# FPGA.net
KiCad netlist of a schematic drawn in Altium Designer
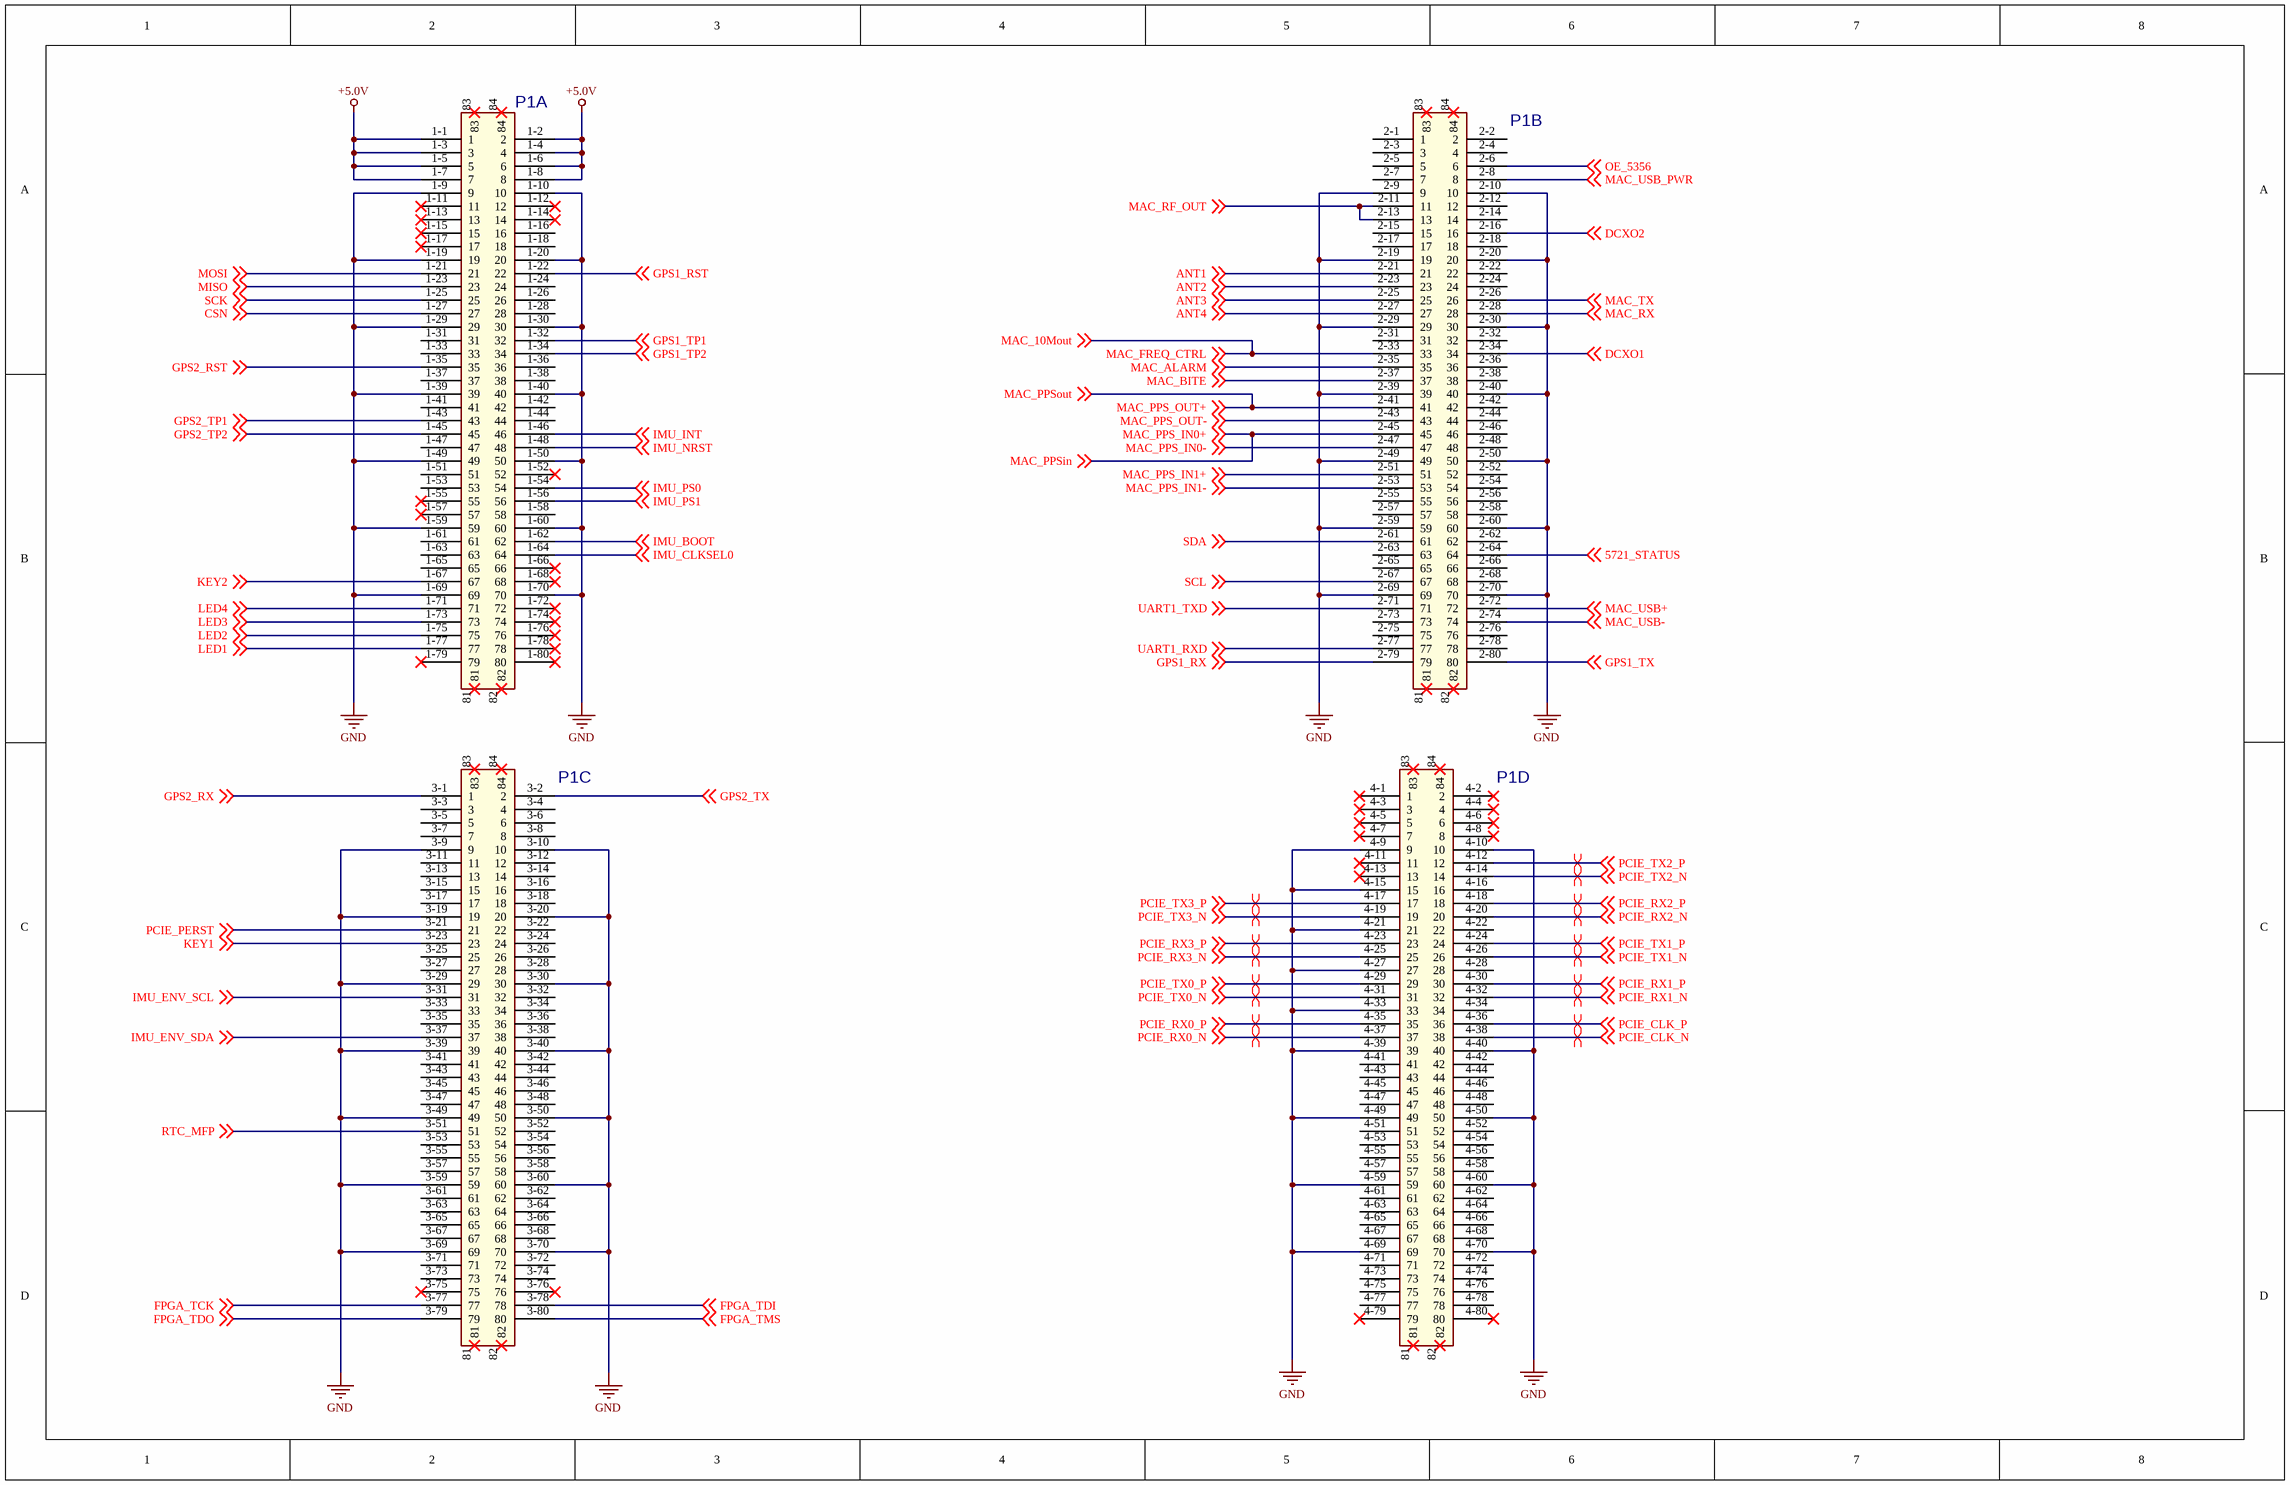
[diagram p0: FPGA.SchDoc]

(export (version "E")
  (design (tool "Eeschema 10.0.6"))
  (components
    (comp (ref "P1")
      (value "MOD, FPGA, AC7100")
      (footprint "ALINX_FPGA")
      (description "MOD, FPGA, AC7100")
      (fields (field (name "MFG PART NUM") "AXK680337YG") (field (name "VALENTIUM PART NUM") "<VALENTIUM>"))
      (libsource (lib "Modules") (part "ALINX_FPGA"))
    )
  )
  (nets
    (net (code "1") (name "+5.0V") (class "Default")
      (node (ref "P1") (pin "1-1") (pinfunction "1_1-1") (pintype "passive"))
      (node (ref "P1") (pin "1-2") (pinfunction "2_1-2") (pintype "passive"))
      (node (ref "P1") (pin "1-3") (pinfunction "3_1-3") (pintype "passive"))
      (node (ref "P1") (pin "1-4") (pinfunction "4_1-4") (pintype "passive"))
      (node (ref "P1") (pin "1-5") (pinfunction "5_1-5") (pintype "passive"))
      (node (ref "P1") (pin "1-6") (pinfunction "6_1-6") (pintype "passive"))
      (node (ref "P1") (pin "1-7") (pinfunction "7_1-7") (pintype "passive"))
      (node (ref "P1") (pin "1-8") (pinfunction "8_1-8") (pintype "passive"))
    )
    (net (code "2") (name "5721_STATUS") (class "Default")
      (node (ref "P1") (pin "2-64") (pinfunction "64_2-64") (pintype "passive"))
    )
    (net (code "3") (name "ANT1") (class "Default")
      (node (ref "P1") (pin "2-21") (pinfunction "21_2-21") (pintype "passive"))
    )
    (net (code "4") (name "ANT2") (class "Default")
      (node (ref "P1") (pin "2-23") (pinfunction "23_2-23") (pintype "passive"))
    )
    (net (code "5") (name "ANT3") (class "Default")
      (node (ref "P1") (pin "2-25") (pinfunction "25_2-25") (pintype "passive"))
    )
    (net (code "6") (name "ANT4") (class "Default")
      (node (ref "P1") (pin "2-27") (pinfunction "27_2-27") (pintype "passive"))
    )
    (net (code "7") (name "CSN") (class "Default")
      (node (ref "P1") (pin "1-27") (pinfunction "27_1-27") (pintype "passive"))
    )
    (net (code "8") (name "DCXO1") (class "Default")
      (node (ref "P1") (pin "2-34") (pinfunction "34_2-34") (pintype "passive"))
    )
    (net (code "9") (name "DCXO2") (class "Default")
      (node (ref "P1") (pin "2-16") (pinfunction "16_2-16") (pintype "passive"))
    )
    (net (code "10") (name "FPGA_TCK") (class "Default")
      (node (ref "P1") (pin "3-77") (pinfunction "77_3-77") (pintype "passive"))
    )
    (net (code "11") (name "FPGA_TDI") (class "Default")
      (node (ref "P1") (pin "3-78") (pinfunction "78_3-78") (pintype "passive"))
    )
    (net (code "12") (name "FPGA_TDO") (class "Default")
      (node (ref "P1") (pin "3-79") (pinfunction "79_3-79") (pintype "passive"))
    )
    (net (code "13") (name "FPGA_TMS") (class "Default")
      (node (ref "P1") (pin "3-80") (pinfunction "80_3-80") (pintype "passive"))
    )
    (net (code "14") (name "GND") (class "Default")
      (node (ref "P1") (pin "1-10") (pinfunction "10_1-10") (pintype "passive"))
      (node (ref "P1") (pin "1-19") (pinfunction "19_1-19") (pintype "passive"))
      (node (ref "P1") (pin "1-20") (pinfunction "20_1-20") (pintype "passive"))
      (node (ref "P1") (pin "1-29") (pinfunction "29_1-29") (pintype "passive"))
      (node (ref "P1") (pin "1-30") (pinfunction "30_1-30") (pintype "passive"))
      (node (ref "P1") (pin "1-39") (pinfunction "39_1-39") (pintype "passive"))
      (node (ref "P1") (pin "1-40") (pinfunction "40_1-40") (pintype "passive"))
      (node (ref "P1") (pin "1-49") (pinfunction "49_1-49") (pintype "passive"))
      (node (ref "P1") (pin "1-50") (pinfunction "50_1-50") (pintype "passive"))
      (node (ref "P1") (pin "1-59") (pinfunction "59_1-59") (pintype "passive"))
      (node (ref "P1") (pin "1-60") (pinfunction "60_1-60") (pintype "passive"))
      (node (ref "P1") (pin "1-69") (pinfunction "69_1-69") (pintype "passive"))
      (node (ref "P1") (pin "1-70") (pinfunction "70_1-70") (pintype "passive"))
      (node (ref "P1") (pin "1-9") (pinfunction "9_1-9") (pintype "passive"))
      (node (ref "P1") (pin "2-10") (pinfunction "10_2-10") (pintype "passive"))
      (node (ref "P1") (pin "2-19") (pinfunction "19_2-19") (pintype "passive"))
      (node (ref "P1") (pin "2-20") (pinfunction "20_2-20") (pintype "passive"))
      (node (ref "P1") (pin "2-29") (pinfunction "29_2-29") (pintype "passive"))
      (node (ref "P1") (pin "2-30") (pinfunction "30_2-30") (pintype "passive"))
      (node (ref "P1") (pin "2-39") (pinfunction "39_2-39") (pintype "passive"))
      (node (ref "P1") (pin "2-40") (pinfunction "40_2-40") (pintype "passive"))
      (node (ref "P1") (pin "2-49") (pinfunction "49_2-49") (pintype "passive"))
      (node (ref "P1") (pin "2-50") (pinfunction "50_2-50") (pintype "passive"))
      (node (ref "P1") (pin "2-59") (pinfunction "59_2-59") (pintype "passive"))
      (node (ref "P1") (pin "2-60") (pinfunction "60_2-60") (pintype "passive"))
      (node (ref "P1") (pin "2-69") (pinfunction "69_2-69") (pintype "passive"))
      (node (ref "P1") (pin "2-70") (pinfunction "70_2-70") (pintype "passive"))
      (node (ref "P1") (pin "2-9") (pinfunction "9_2-9") (pintype "passive"))
      (node (ref "P1") (pin "3-10") (pinfunction "10_3-10") (pintype "passive"))
      (node (ref "P1") (pin "3-19") (pinfunction "19_3-19") (pintype "passive"))
      (node (ref "P1") (pin "3-20") (pinfunction "20_3-20") (pintype "passive"))
      (node (ref "P1") (pin "3-29") (pinfunction "29_3-29") (pintype "passive"))
      (node (ref "P1") (pin "3-30") (pinfunction "30_3-30") (pintype "passive"))
      (node (ref "P1") (pin "3-39") (pinfunction "39_3-39") (pintype "passive"))
      (node (ref "P1") (pin "3-40") (pinfunction "40_3-40") (pintype "passive"))
      (node (ref "P1") (pin "3-49") (pinfunction "49_3-49") (pintype "passive"))
      (node (ref "P1") (pin "3-50") (pinfunction "50_3-50") (pintype "passive"))
      (node (ref "P1") (pin "3-59") (pinfunction "59_3-59") (pintype "passive"))
      (node (ref "P1") (pin "3-60") (pinfunction "60_3-60") (pintype "passive"))
      (node (ref "P1") (pin "3-69") (pinfunction "69_3-69") (pintype "passive"))
      (node (ref "P1") (pin "3-70") (pinfunction "70_3-70") (pintype "passive"))
      (node (ref "P1") (pin "3-9") (pinfunction "9_3-9") (pintype "passive"))
      (node (ref "P1") (pin "4-10") (pinfunction "10_4-10") (pintype "passive"))
      (node (ref "P1") (pin "4-15") (pinfunction "15_4-15") (pintype "passive"))
      (node (ref "P1") (pin "4-21") (pinfunction "21_4-21") (pintype "passive"))
      (node (ref "P1") (pin "4-27") (pinfunction "27_4-27") (pintype "passive"))
      (node (ref "P1") (pin "4-33") (pinfunction "33_4-33") (pintype "passive"))
      (node (ref "P1") (pin "4-39") (pinfunction "39_4-39") (pintype "passive"))
      (node (ref "P1") (pin "4-40") (pinfunction "40_4-40") (pintype "passive"))
      (node (ref "P1") (pin "4-49") (pinfunction "49_4-49") (pintype "passive"))
      (node (ref "P1") (pin "4-50") (pinfunction "50_4-50") (pintype "passive"))
      (node (ref "P1") (pin "4-59") (pinfunction "59_4-59") (pintype "passive"))
      (node (ref "P1") (pin "4-60") (pinfunction "60_4-60") (pintype "passive"))
      (node (ref "P1") (pin "4-69") (pinfunction "69_4-69") (pintype "passive"))
      (node (ref "P1") (pin "4-70") (pinfunction "70_4-70") (pintype "passive"))
      (node (ref "P1") (pin "4-9") (pinfunction "9_4-9") (pintype "passive"))
    )
    (net (code "15") (name "GPS1_RST") (class "Default")
      (node (ref "P1") (pin "1-22") (pinfunction "22_1-22") (pintype "passive"))
    )
    (net (code "16") (name "GPS1_RX") (class "Default")
      (node (ref "P1") (pin "2-79") (pinfunction "79_2-79") (pintype "passive"))
    )
    (net (code "17") (name "GPS1_TP1") (class "Default")
      (node (ref "P1") (pin "1-32") (pinfunction "32_1-32") (pintype "passive"))
    )
    (net (code "18") (name "GPS1_TP2") (class "Default")
      (node (ref "P1") (pin "1-34") (pinfunction "34_1-34") (pintype "passive"))
    )
    (net (code "19") (name "GPS1_TX") (class "Default")
      (node (ref "P1") (pin "2-80") (pinfunction "80_2-80") (pintype "passive"))
    )
    (net (code "20") (name "GPS2_RST") (class "Default")
      (node (ref "P1") (pin "1-35") (pinfunction "35_1-35") (pintype "passive"))
    )
    (net (code "21") (name "GPS2_RX") (class "Default")
      (node (ref "P1") (pin "3-1") (pinfunction "1_3-1") (pintype "passive"))
    )
    (net (code "22") (name "GPS2_TP1") (class "Default")
      (node (ref "P1") (pin "1-43") (pinfunction "43_1-43") (pintype "passive"))
    )
    (net (code "23") (name "GPS2_TP2") (class "Default")
      (node (ref "P1") (pin "1-45") (pinfunction "45_1-45") (pintype "passive"))
    )
    (net (code "24") (name "GPS2_TX") (class "Default")
      (node (ref "P1") (pin "3-2") (pinfunction "2_3-2") (pintype "passive"))
    )
    (net (code "25") (name "IMU_BOOT") (class "Default")
      (node (ref "P1") (pin "1-62") (pinfunction "62_1-62") (pintype "passive"))
    )
    (net (code "26") (name "IMU_CLKSEL0") (class "Default")
      (node (ref "P1") (pin "1-64") (pinfunction "64_1-64") (pintype "passive"))
    )
    (net (code "27") (name "IMU_ENV_SCL") (class "Default")
      (node (ref "P1") (pin "3-31") (pinfunction "31_3-31") (pintype "passive"))
    )
    (net (code "28") (name "IMU_ENV_SDA") (class "Default")
      (node (ref "P1") (pin "3-37") (pinfunction "37_3-37") (pintype "passive"))
    )
    (net (code "29") (name "IMU_INT") (class "Default")
      (node (ref "P1") (pin "1-46") (pinfunction "46_1-46") (pintype "passive"))
    )
    (net (code "30") (name "IMU_NRST") (class "Default")
      (node (ref "P1") (pin "1-48") (pinfunction "48_1-48") (pintype "passive"))
    )
    (net (code "31") (name "IMU_PS0") (class "Default")
      (node (ref "P1") (pin "1-54") (pinfunction "54_1-54") (pintype "passive"))
    )
    (net (code "32") (name "IMU_PS1") (class "Default")
      (node (ref "P1") (pin "1-56") (pinfunction "56_1-56") (pintype "passive"))
    )
    (net (code "33") (name "KEY1") (class "Default")
      (node (ref "P1") (pin "3-23") (pinfunction "23_3-23") (pintype "passive"))
    )
    (net (code "34") (name "KEY2") (class "Default")
      (node (ref "P1") (pin "1-67") (pinfunction "67_1-67") (pintype "passive"))
    )
    (net (code "35") (name "LED1") (class "Default")
      (node (ref "P1") (pin "1-77") (pinfunction "77_1-77") (pintype "passive"))
    )
    (net (code "36") (name "LED2") (class "Default")
      (node (ref "P1") (pin "1-75") (pinfunction "75_1-75") (pintype "passive"))
    )
    (net (code "37") (name "LED3") (class "Default")
      (node (ref "P1") (pin "1-73") (pinfunction "73_1-73") (pintype "passive"))
    )
    (net (code "38") (name "LED4") (class "Default")
      (node (ref "P1") (pin "1-71") (pinfunction "71_1-71") (pintype "passive"))
    )
    (net (code "39") (name "MAC_10Mout") (class "Default")
      (node (ref "P1") (pin "2-33") (pinfunction "33_2-33") (pintype "passive"))
    )
    (net (code "40") (name "MAC_ALARM") (class "Default")
      (node (ref "P1") (pin "2-35") (pinfunction "35_2-35") (pintype "passive"))
    )
    (net (code "41") (name "MAC_BITE") (class "Default")
      (node (ref "P1") (pin "2-37") (pinfunction "37_2-37") (pintype "passive"))
    )
    (net (code "42") (name "MAC_PPS_IN0+") (class "Default")
      (node (ref "P1") (pin "2-45") (pinfunction "45_2-45") (pintype "passive"))
    )
    (net (code "43") (name "MAC_PPS_IN0-") (class "Default")
      (node (ref "P1") (pin "2-47") (pinfunction "47_2-47") (pintype "passive"))
    )
    (net (code "44") (name "MAC_PPS_IN1+") (class "Default")
      (node (ref "P1") (pin "2-51") (pinfunction "51_2-51") (pintype "passive"))
    )
    (net (code "45") (name "MAC_PPS_IN1-") (class "Default")
      (node (ref "P1") (pin "2-53") (pinfunction "53_2-53") (pintype "passive"))
    )
    (net (code "46") (name "MAC_PPS_OUT+") (class "Default")
      (node (ref "P1") (pin "2-41") (pinfunction "41_2-41") (pintype "passive"))
    )
    (net (code "47") (name "MAC_PPS_OUT-") (class "Default")
      (node (ref "P1") (pin "2-43") (pinfunction "43_2-43") (pintype "passive"))
    )
    (net (code "48") (name "MAC_RF_OUT") (class "Default")
      (node (ref "P1") (pin "2-11") (pinfunction "11_2-11") (pintype "passive"))
      (node (ref "P1") (pin "2-13") (pinfunction "13_2-13") (pintype "passive"))
    )
    (net (code "49") (name "MAC_RX") (class "Default")
      (node (ref "P1") (pin "2-28") (pinfunction "28_2-28") (pintype "passive"))
    )
    (net (code "50") (name "MAC_TX") (class "Default")
      (node (ref "P1") (pin "2-26") (pinfunction "26_2-26") (pintype "passive"))
    )
    (net (code "51") (name "MAC_USB+") (class "Default")
      (node (ref "P1") (pin "2-72") (pinfunction "72_2-72") (pintype "passive"))
    )
    (net (code "52") (name "MAC_USB-") (class "Default")
      (node (ref "P1") (pin "2-74") (pinfunction "74_2-74") (pintype "passive"))
    )
    (net (code "53") (name "MAC_USB_PWR") (class "Default")
      (node (ref "P1") (pin "2-8") (pinfunction "8_2-8") (pintype "passive"))
    )
    (net (code "54") (name "MISO") (class "Default")
      (node (ref "P1") (pin "1-23") (pinfunction "23_1-23") (pintype "passive"))
    )
    (net (code "55") (name "MOSI") (class "Default")
      (node (ref "P1") (pin "1-21") (pinfunction "21_1-21") (pintype "passive"))
    )
    (net (code "56") (name "OE_5356") (class "Default")
      (node (ref "P1") (pin "2-6") (pinfunction "6_2-6") (pintype "passive"))
    )
    (net (code "57") (name "PCIE_CLK_N") (class "Default")
      (node (ref "P1") (pin "4-38") (pinfunction "38_4-38") (pintype "passive"))
    )
    (net (code "58") (name "PCIE_CLK_P") (class "Default")
      (node (ref "P1") (pin "4-36") (pinfunction "36_4-36") (pintype "passive"))
    )
    (net (code "59") (name "PCIE_PERST") (class "Default")
      (node (ref "P1") (pin "3-21") (pinfunction "21_3-21") (pintype "passive"))
    )
    (net (code "60") (name "PCIE_RX0_N") (class "Default")
      (node (ref "P1") (pin "4-37") (pinfunction "37_4-37") (pintype "passive"))
    )
    (net (code "61") (name "PCIE_RX0_P") (class "Default")
      (node (ref "P1") (pin "4-35") (pinfunction "35_4-35") (pintype "passive"))
    )
    (net (code "62") (name "PCIE_RX1_N") (class "Default")
      (node (ref "P1") (pin "4-32") (pinfunction "32_4-32") (pintype "passive"))
    )
    (net (code "63") (name "PCIE_RX1_P") (class "Default")
      (node (ref "P1") (pin "4-30") (pinfunction "30_4-30") (pintype "passive"))
    )
    (net (code "64") (name "PCIE_RX2_N") (class "Default")
      (node (ref "P1") (pin "4-20") (pinfunction "20_4-20") (pintype "passive"))
    )
    (net (code "65") (name "PCIE_RX2_P") (class "Default")
      (node (ref "P1") (pin "4-18") (pinfunction "18_4-18") (pintype "passive"))
    )
    (net (code "66") (name "PCIE_RX3_N") (class "Default")
      (node (ref "P1") (pin "4-25") (pinfunction "25_4-25") (pintype "passive"))
    )
    (net (code "67") (name "PCIE_RX3_P") (class "Default")
      (node (ref "P1") (pin "4-23") (pinfunction "23_4-23") (pintype "passive"))
    )
    (net (code "68") (name "PCIE_TX0_N") (class "Default")
      (node (ref "P1") (pin "4-31") (pinfunction "31_4-31") (pintype "passive"))
    )
    (net (code "69") (name "PCIE_TX0_P") (class "Default")
      (node (ref "P1") (pin "4-29") (pinfunction "29_4-29") (pintype "passive"))
    )
    (net (code "70") (name "PCIE_TX1_N") (class "Default")
      (node (ref "P1") (pin "4-26") (pinfunction "26_4-26") (pintype "passive"))
    )
    (net (code "71") (name "PCIE_TX1_P") (class "Default")
      (node (ref "P1") (pin "4-24") (pinfunction "24_4-24") (pintype "passive"))
    )
    (net (code "72") (name "PCIE_TX2_N") (class "Default")
      (node (ref "P1") (pin "4-14") (pinfunction "14_4-14") (pintype "passive"))
    )
    (net (code "73") (name "PCIE_TX2_P") (class "Default")
      (node (ref "P1") (pin "4-12") (pinfunction "12_4-12") (pintype "passive"))
    )
    (net (code "74") (name "PCIE_TX3_N") (class "Default")
      (node (ref "P1") (pin "4-19") (pinfunction "19_4-19") (pintype "passive"))
    )
    (net (code "75") (name "PCIE_TX3_P") (class "Default")
      (node (ref "P1") (pin "4-17") (pinfunction "17_4-17") (pintype "passive"))
    )
    (net (code "76") (name "RTC_MFP") (class "Default")
      (node (ref "P1") (pin "3-51") (pinfunction "51_3-51") (pintype "passive"))
    )
    (net (code "77") (name "SCK") (class "Default")
      (node (ref "P1") (pin "1-25") (pinfunction "25_1-25") (pintype "passive"))
    )
    (net (code "78") (name "SCL") (class "Default")
      (node (ref "P1") (pin "2-67") (pinfunction "67_2-67") (pintype "passive"))
    )
    (net (code "79") (name "SDA") (class "Default")
      (node (ref "P1") (pin "2-61") (pinfunction "61_2-61") (pintype "passive"))
    )
    (net (code "80") (name "UART1_RXD") (class "Default")
      (node (ref "P1") (pin "2-77") (pinfunction "77_2-77") (pintype "passive"))
    )
    (net (code "81") (name "UART1_TXD") (class "Default")
      (node (ref "P1") (pin "2-71") (pinfunction "71_2-71") (pintype "passive"))
    )
    (net (code "82") (name "unconnected-(P1-Pad81)") (class "Default")
      (node (ref "P1") (pin "81") (pinfunction "81_81") (pintype "passive+no_connect"))
    )
    (net (code "83") (name "unconnected-(P1-Pad81)_1") (class "Default")
      (node (ref "P1") (pin "81") (pinfunction "81_81") (pintype "passive+no_connect"))
    )
    (net (code "84") (name "unconnected-(P1-Pad81)_2") (class "Default")
      (node (ref "P1") (pin "81") (pinfunction "81_81") (pintype "passive+no_connect"))
    )
    (net (code "85") (name "unconnected-(P1-Pad81)_3") (class "Default")
      (node (ref "P1") (pin "81") (pinfunction "81_81") (pintype "passive+no_connect"))
    )
    (net (code "86") (name "unconnected-(P1-Pad82)") (class "Default")
      (node (ref "P1") (pin "82") (pinfunction "82_82") (pintype "passive+no_connect"))
    )
    (net (code "87") (name "unconnected-(P1-Pad82)_1") (class "Default")
      (node (ref "P1") (pin "82") (pinfunction "82_82") (pintype "passive+no_connect"))
    )
    (net (code "88") (name "unconnected-(P1-Pad82)_2") (class "Default")
      (node (ref "P1") (pin "82") (pinfunction "82_82") (pintype "passive+no_connect"))
    )
    (net (code "89") (name "unconnected-(P1-Pad82)_3") (class "Default")
      (node (ref "P1") (pin "82") (pinfunction "82_82") (pintype "passive+no_connect"))
    )
    (net (code "90") (name "unconnected-(P1-Pad83)") (class "Default")
      (node (ref "P1") (pin "83") (pinfunction "83_83") (pintype "passive+no_connect"))
    )
    (net (code "91") (name "unconnected-(P1-Pad83)_1") (class "Default")
      (node (ref "P1") (pin "83") (pinfunction "83_83") (pintype "passive+no_connect"))
    )
    (net (code "92") (name "unconnected-(P1-Pad83)_2") (class "Default")
      (node (ref "P1") (pin "83") (pinfunction "83_83") (pintype "passive+no_connect"))
    )
    (net (code "93") (name "unconnected-(P1-Pad83)_3") (class "Default")
      (node (ref "P1") (pin "83") (pinfunction "83_83") (pintype "passive+no_connect"))
    )
    (net (code "94") (name "unconnected-(P1-Pad84)") (class "Default")
      (node (ref "P1") (pin "84") (pinfunction "84_84") (pintype "passive+no_connect"))
    )
    (net (code "95") (name "unconnected-(P1-Pad84)_1") (class "Default")
      (node (ref "P1") (pin "84") (pinfunction "84_84") (pintype "passive+no_connect"))
    )
    (net (code "96") (name "unconnected-(P1-Pad84)_2") (class "Default")
      (node (ref "P1") (pin "84") (pinfunction "84_84") (pintype "passive+no_connect"))
    )
    (net (code "97") (name "unconnected-(P1-Pad84)_3") (class "Default")
      (node (ref "P1") (pin "84") (pinfunction "84_84") (pintype "passive+no_connect"))
    )
    (net (code "98") (name "unconnected-(P1A-11-Pad1-11)") (class "Default")
      (node (ref "P1") (pin "1-11") (pinfunction "11_1-11") (pintype "passive+no_connect"))
    )
    (net (code "99") (name "unconnected-(P1A-12-Pad1-12)") (class "Default")
      (node (ref "P1") (pin "1-12") (pinfunction "12_1-12") (pintype "passive+no_connect"))
    )
    (net (code "100") (name "unconnected-(P1A-13-Pad1-13)") (class "Default")
      (node (ref "P1") (pin "1-13") (pinfunction "13_1-13") (pintype "passive+no_connect"))
    )
    (net (code "101") (name "unconnected-(P1A-14-Pad1-14)") (class "Default")
      (node (ref "P1") (pin "1-14") (pinfunction "14_1-14") (pintype "passive+no_connect"))
    )
    (net (code "102") (name "unconnected-(P1A-15-Pad1-15)") (class "Default")
      (node (ref "P1") (pin "1-15") (pinfunction "15_1-15") (pintype "passive+no_connect"))
    )
    (net (code "103") (name "unconnected-(P1A-16-Pad1-16)") (class "Default")
      (node (ref "P1") (pin "1-16") (pinfunction "16_1-16") (pintype "passive"))
    )
    (net (code "104") (name "unconnected-(P1A-17-Pad1-17)") (class "Default")
      (node (ref "P1") (pin "1-17") (pinfunction "17_1-17") (pintype "passive+no_connect"))
    )
    (net (code "105") (name "unconnected-(P1A-18-Pad1-18)") (class "Default")
      (node (ref "P1") (pin "1-18") (pinfunction "18_1-18") (pintype "passive"))
    )
    (net (code "106") (name "unconnected-(P1A-24-Pad1-24)") (class "Default")
      (node (ref "P1") (pin "1-24") (pinfunction "24_1-24") (pintype "passive"))
    )
    (net (code "107") (name "unconnected-(P1A-26-Pad1-26)") (class "Default")
      (node (ref "P1") (pin "1-26") (pinfunction "26_1-26") (pintype "passive"))
    )
    (net (code "108") (name "unconnected-(P1A-28-Pad1-28)") (class "Default")
      (node (ref "P1") (pin "1-28") (pinfunction "28_1-28") (pintype "passive"))
    )
    (net (code "109") (name "unconnected-(P1A-31-Pad1-31)") (class "Default")
      (node (ref "P1") (pin "1-31") (pinfunction "31_1-31") (pintype "passive"))
    )
    (net (code "110") (name "unconnected-(P1A-33-Pad1-33)") (class "Default")
      (node (ref "P1") (pin "1-33") (pinfunction "33_1-33") (pintype "passive"))
    )
    (net (code "111") (name "unconnected-(P1A-36-Pad1-36)") (class "Default")
      (node (ref "P1") (pin "1-36") (pinfunction "36_1-36") (pintype "passive"))
    )
    (net (code "112") (name "unconnected-(P1A-37-Pad1-37)") (class "Default")
      (node (ref "P1") (pin "1-37") (pinfunction "37_1-37") (pintype "passive"))
    )
    (net (code "113") (name "unconnected-(P1A-38-Pad1-38)") (class "Default")
      (node (ref "P1") (pin "1-38") (pinfunction "38_1-38") (pintype "passive"))
    )
    (net (code "114") (name "unconnected-(P1A-41-Pad1-41)") (class "Default")
      (node (ref "P1") (pin "1-41") (pinfunction "41_1-41") (pintype "passive"))
    )
    (net (code "115") (name "unconnected-(P1A-42-Pad1-42)") (class "Default")
      (node (ref "P1") (pin "1-42") (pinfunction "42_1-42") (pintype "passive"))
    )
    (net (code "116") (name "unconnected-(P1A-44-Pad1-44)") (class "Default")
      (node (ref "P1") (pin "1-44") (pinfunction "44_1-44") (pintype "passive"))
    )
    (net (code "117") (name "unconnected-(P1A-47-Pad1-47)") (class "Default")
      (node (ref "P1") (pin "1-47") (pinfunction "47_1-47") (pintype "passive"))
    )
    (net (code "118") (name "unconnected-(P1A-51-Pad1-51)") (class "Default")
      (node (ref "P1") (pin "1-51") (pinfunction "51_1-51") (pintype "passive"))
    )
    (net (code "119") (name "unconnected-(P1A-52-Pad1-52)") (class "Default")
      (node (ref "P1") (pin "1-52") (pinfunction "52_1-52") (pintype "passive+no_connect"))
    )
    (net (code "120") (name "unconnected-(P1A-53-Pad1-53)") (class "Default")
      (node (ref "P1") (pin "1-53") (pinfunction "53_1-53") (pintype "passive"))
    )
    (net (code "121") (name "unconnected-(P1A-55-Pad1-55)") (class "Default")
      (node (ref "P1") (pin "1-55") (pinfunction "55_1-55") (pintype "passive+no_connect"))
    )
    (net (code "122") (name "unconnected-(P1A-57-Pad1-57)") (class "Default")
      (node (ref "P1") (pin "1-57") (pinfunction "57_1-57") (pintype "passive+no_connect"))
    )
    (net (code "123") (name "unconnected-(P1A-58-Pad1-58)") (class "Default")
      (node (ref "P1") (pin "1-58") (pinfunction "58_1-58") (pintype "passive"))
    )
    (net (code "124") (name "unconnected-(P1A-61-Pad1-61)") (class "Default")
      (node (ref "P1") (pin "1-61") (pinfunction "61_1-61") (pintype "passive"))
    )
    (net (code "125") (name "unconnected-(P1A-63-Pad1-63)") (class "Default")
      (node (ref "P1") (pin "1-63") (pinfunction "63_1-63") (pintype "passive"))
    )
    (net (code "126") (name "unconnected-(P1A-65-Pad1-65)") (class "Default")
      (node (ref "P1") (pin "1-65") (pinfunction "65_1-65") (pintype "passive"))
    )
    (net (code "127") (name "unconnected-(P1A-66-Pad1-66)") (class "Default")
      (node (ref "P1") (pin "1-66") (pinfunction "66_1-66") (pintype "passive+no_connect"))
    )
    (net (code "128") (name "unconnected-(P1A-68-Pad1-68)") (class "Default")
      (node (ref "P1") (pin "1-68") (pinfunction "68_1-68") (pintype "passive+no_connect"))
    )
    (net (code "129") (name "unconnected-(P1A-72-Pad1-72)") (class "Default")
      (node (ref "P1") (pin "1-72") (pinfunction "72_1-72") (pintype "passive+no_connect"))
    )
    (net (code "130") (name "unconnected-(P1A-74-Pad1-74)") (class "Default")
      (node (ref "P1") (pin "1-74") (pinfunction "74_1-74") (pintype "passive+no_connect"))
    )
    (net (code "131") (name "unconnected-(P1A-76-Pad1-76)") (class "Default")
      (node (ref "P1") (pin "1-76") (pinfunction "76_1-76") (pintype "passive+no_connect"))
    )
    (net (code "132") (name "unconnected-(P1A-78-Pad1-78)") (class "Default")
      (node (ref "P1") (pin "1-78") (pinfunction "78_1-78") (pintype "passive+no_connect"))
    )
    (net (code "133") (name "unconnected-(P1A-79-Pad1-79)") (class "Default")
      (node (ref "P1") (pin "1-79") (pinfunction "79_1-79") (pintype "passive+no_connect"))
    )
    (net (code "134") (name "unconnected-(P1A-80-Pad1-80)") (class "Default")
      (node (ref "P1") (pin "1-80") (pinfunction "80_1-80") (pintype "passive+no_connect"))
    )
    (net (code "135") (name "unconnected-(P1B-1-Pad2-1)") (class "Default")
      (node (ref "P1") (pin "2-1") (pinfunction "1_2-1") (pintype "passive"))
    )
    (net (code "136") (name "unconnected-(P1B-2-Pad2-2)") (class "Default")
      (node (ref "P1") (pin "2-2") (pinfunction "2_2-2") (pintype "passive"))
    )
    (net (code "137") (name "unconnected-(P1B-3-Pad2-3)") (class "Default")
      (node (ref "P1") (pin "2-3") (pinfunction "3_2-3") (pintype "passive"))
    )
    (net (code "138") (name "unconnected-(P1B-4-Pad2-4)") (class "Default")
      (node (ref "P1") (pin "2-4") (pinfunction "4_2-4") (pintype "passive"))
    )
    (net (code "139") (name "unconnected-(P1B-5-Pad2-5)") (class "Default")
      (node (ref "P1") (pin "2-5") (pinfunction "5_2-5") (pintype "passive"))
    )
    (net (code "140") (name "unconnected-(P1B-7-Pad2-7)") (class "Default")
      (node (ref "P1") (pin "2-7") (pinfunction "7_2-7") (pintype "passive"))
    )
    (net (code "141") (name "unconnected-(P1B-12-Pad2-12)") (class "Default")
      (node (ref "P1") (pin "2-12") (pinfunction "12_2-12") (pintype "passive"))
    )
    (net (code "142") (name "unconnected-(P1B-14-Pad2-14)") (class "Default")
      (node (ref "P1") (pin "2-14") (pinfunction "14_2-14") (pintype "passive"))
    )
    (net (code "143") (name "unconnected-(P1B-15-Pad2-15)") (class "Default")
      (node (ref "P1") (pin "2-15") (pinfunction "15_2-15") (pintype "passive"))
    )
    (net (code "144") (name "unconnected-(P1B-17-Pad2-17)") (class "Default")
      (node (ref "P1") (pin "2-17") (pinfunction "17_2-17") (pintype "passive"))
    )
    (net (code "145") (name "unconnected-(P1B-18-Pad2-18)") (class "Default")
      (node (ref "P1") (pin "2-18") (pinfunction "18_2-18") (pintype "passive"))
    )
    (net (code "146") (name "unconnected-(P1B-22-Pad2-22)") (class "Default")
      (node (ref "P1") (pin "2-22") (pinfunction "22_2-22") (pintype "passive"))
    )
    (net (code "147") (name "unconnected-(P1B-24-Pad2-24)") (class "Default")
      (node (ref "P1") (pin "2-24") (pinfunction "24_2-24") (pintype "passive"))
    )
    (net (code "148") (name "unconnected-(P1B-31-Pad2-31)") (class "Default")
      (node (ref "P1") (pin "2-31") (pinfunction "31_2-31") (pintype "passive"))
    )
    (net (code "149") (name "unconnected-(P1B-32-Pad2-32)") (class "Default")
      (node (ref "P1") (pin "2-32") (pinfunction "32_2-32") (pintype "passive"))
    )
    (net (code "150") (name "unconnected-(P1B-36-Pad2-36)") (class "Default")
      (node (ref "P1") (pin "2-36") (pinfunction "36_2-36") (pintype "passive"))
    )
    (net (code "151") (name "unconnected-(P1B-38-Pad2-38)") (class "Default")
      (node (ref "P1") (pin "2-38") (pinfunction "38_2-38") (pintype "passive"))
    )
    (net (code "152") (name "unconnected-(P1B-42-Pad2-42)") (class "Default")
      (node (ref "P1") (pin "2-42") (pinfunction "42_2-42") (pintype "passive"))
    )
    (net (code "153") (name "unconnected-(P1B-44-Pad2-44)") (class "Default")
      (node (ref "P1") (pin "2-44") (pinfunction "44_2-44") (pintype "passive"))
    )
    (net (code "154") (name "unconnected-(P1B-46-Pad2-46)") (class "Default")
      (node (ref "P1") (pin "2-46") (pinfunction "46_2-46") (pintype "passive"))
    )
    (net (code "155") (name "unconnected-(P1B-48-Pad2-48)") (class "Default")
      (node (ref "P1") (pin "2-48") (pinfunction "48_2-48") (pintype "passive"))
    )
    (net (code "156") (name "unconnected-(P1B-52-Pad2-52)") (class "Default")
      (node (ref "P1") (pin "2-52") (pinfunction "52_2-52") (pintype "passive"))
    )
    (net (code "157") (name "unconnected-(P1B-54-Pad2-54)") (class "Default")
      (node (ref "P1") (pin "2-54") (pinfunction "54_2-54") (pintype "passive"))
    )
    (net (code "158") (name "unconnected-(P1B-55-Pad2-55)") (class "Default")
      (node (ref "P1") (pin "2-55") (pinfunction "55_2-55") (pintype "passive"))
    )
    (net (code "159") (name "unconnected-(P1B-56-Pad2-56)") (class "Default")
      (node (ref "P1") (pin "2-56") (pinfunction "56_2-56") (pintype "passive"))
    )
    (net (code "160") (name "unconnected-(P1B-57-Pad2-57)") (class "Default")
      (node (ref "P1") (pin "2-57") (pinfunction "57_2-57") (pintype "passive"))
    )
    (net (code "161") (name "unconnected-(P1B-58-Pad2-58)") (class "Default")
      (node (ref "P1") (pin "2-58") (pinfunction "58_2-58") (pintype "passive"))
    )
    (net (code "162") (name "unconnected-(P1B-62-Pad2-62)") (class "Default")
      (node (ref "P1") (pin "2-62") (pinfunction "62_2-62") (pintype "passive"))
    )
    (net (code "163") (name "unconnected-(P1B-63-Pad2-63)") (class "Default")
      (node (ref "P1") (pin "2-63") (pinfunction "63_2-63") (pintype "passive"))
    )
    (net (code "164") (name "unconnected-(P1B-65-Pad2-65)") (class "Default")
      (node (ref "P1") (pin "2-65") (pinfunction "65_2-65") (pintype "passive"))
    )
    (net (code "165") (name "unconnected-(P1B-66-Pad2-66)") (class "Default")
      (node (ref "P1") (pin "2-66") (pinfunction "66_2-66") (pintype "passive"))
    )
    (net (code "166") (name "unconnected-(P1B-68-Pad2-68)") (class "Default")
      (node (ref "P1") (pin "2-68") (pinfunction "68_2-68") (pintype "passive"))
    )
    (net (code "167") (name "unconnected-(P1B-73-Pad2-73)") (class "Default")
      (node (ref "P1") (pin "2-73") (pinfunction "73_2-73") (pintype "passive"))
    )
    (net (code "168") (name "unconnected-(P1B-75-Pad2-75)") (class "Default")
      (node (ref "P1") (pin "2-75") (pinfunction "75_2-75") (pintype "passive"))
    )
    (net (code "169") (name "unconnected-(P1B-76-Pad2-76)") (class "Default")
      (node (ref "P1") (pin "2-76") (pinfunction "76_2-76") (pintype "passive"))
    )
    (net (code "170") (name "unconnected-(P1B-78-Pad2-78)") (class "Default")
      (node (ref "P1") (pin "2-78") (pinfunction "78_2-78") (pintype "passive"))
    )
    (net (code "171") (name "unconnected-(P1C-3-Pad3-3)") (class "Default")
      (node (ref "P1") (pin "3-3") (pinfunction "3_3-3") (pintype "passive"))
    )
    (net (code "172") (name "unconnected-(P1C-4-Pad3-4)") (class "Default")
      (node (ref "P1") (pin "3-4") (pinfunction "4_3-4") (pintype "passive"))
    )
    (net (code "173") (name "unconnected-(P1C-5-Pad3-5)") (class "Default")
      (node (ref "P1") (pin "3-5") (pinfunction "5_3-5") (pintype "passive"))
    )
    (net (code "174") (name "unconnected-(P1C-6-Pad3-6)") (class "Default")
      (node (ref "P1") (pin "3-6") (pinfunction "6_3-6") (pintype "passive"))
    )
    (net (code "175") (name "unconnected-(P1C-7-Pad3-7)") (class "Default")
      (node (ref "P1") (pin "3-7") (pinfunction "7_3-7") (pintype "passive"))
    )
    (net (code "176") (name "unconnected-(P1C-8-Pad3-8)") (class "Default")
      (node (ref "P1") (pin "3-8") (pinfunction "8_3-8") (pintype "passive"))
    )
    (net (code "177") (name "unconnected-(P1C-11-Pad3-11)") (class "Default")
      (node (ref "P1") (pin "3-11") (pinfunction "11_3-11") (pintype "passive"))
    )
    (net (code "178") (name "unconnected-(P1C-12-Pad3-12)") (class "Default")
      (node (ref "P1") (pin "3-12") (pinfunction "12_3-12") (pintype "passive"))
    )
    (net (code "179") (name "unconnected-(P1C-13-Pad3-13)") (class "Default")
      (node (ref "P1") (pin "3-13") (pinfunction "13_3-13") (pintype "passive"))
    )
    (net (code "180") (name "unconnected-(P1C-14-Pad3-14)") (class "Default")
      (node (ref "P1") (pin "3-14") (pinfunction "14_3-14") (pintype "passive"))
    )
    (net (code "181") (name "unconnected-(P1C-15-Pad3-15)") (class "Default")
      (node (ref "P1") (pin "3-15") (pinfunction "15_3-15") (pintype "passive"))
    )
    (net (code "182") (name "unconnected-(P1C-16-Pad3-16)") (class "Default")
      (node (ref "P1") (pin "3-16") (pinfunction "16_3-16") (pintype "passive"))
    )
    (net (code "183") (name "unconnected-(P1C-17-Pad3-17)") (class "Default")
      (node (ref "P1") (pin "3-17") (pinfunction "17_3-17") (pintype "passive"))
    )
    (net (code "184") (name "unconnected-(P1C-18-Pad3-18)") (class "Default")
      (node (ref "P1") (pin "3-18") (pinfunction "18_3-18") (pintype "passive"))
    )
    (net (code "185") (name "unconnected-(P1C-22-Pad3-22)") (class "Default")
      (node (ref "P1") (pin "3-22") (pinfunction "22_3-22") (pintype "passive"))
    )
    (net (code "186") (name "unconnected-(P1C-24-Pad3-24)") (class "Default")
      (node (ref "P1") (pin "3-24") (pinfunction "24_3-24") (pintype "passive"))
    )
    (net (code "187") (name "unconnected-(P1C-25-Pad3-25)") (class "Default")
      (node (ref "P1") (pin "3-25") (pinfunction "25_3-25") (pintype "passive"))
    )
    (net (code "188") (name "unconnected-(P1C-26-Pad3-26)") (class "Default")
      (node (ref "P1") (pin "3-26") (pinfunction "26_3-26") (pintype "passive"))
    )
    (net (code "189") (name "unconnected-(P1C-27-Pad3-27)") (class "Default")
      (node (ref "P1") (pin "3-27") (pinfunction "27_3-27") (pintype "passive"))
    )
    (net (code "190") (name "unconnected-(P1C-28-Pad3-28)") (class "Default")
      (node (ref "P1") (pin "3-28") (pinfunction "28_3-28") (pintype "passive"))
    )
    (net (code "191") (name "unconnected-(P1C-32-Pad3-32)") (class "Default")
      (node (ref "P1") (pin "3-32") (pinfunction "32_3-32") (pintype "passive"))
    )
    (net (code "192") (name "unconnected-(P1C-33-Pad3-33)") (class "Default")
      (node (ref "P1") (pin "3-33") (pinfunction "33_3-33") (pintype "passive"))
    )
    (net (code "193") (name "unconnected-(P1C-34-Pad3-34)") (class "Default")
      (node (ref "P1") (pin "3-34") (pinfunction "34_3-34") (pintype "passive"))
    )
    (net (code "194") (name "unconnected-(P1C-35-Pad3-35)") (class "Default")
      (node (ref "P1") (pin "3-35") (pinfunction "35_3-35") (pintype "passive"))
    )
    (net (code "195") (name "unconnected-(P1C-36-Pad3-36)") (class "Default")
      (node (ref "P1") (pin "3-36") (pinfunction "36_3-36") (pintype "passive"))
    )
    (net (code "196") (name "unconnected-(P1C-38-Pad3-38)") (class "Default")
      (node (ref "P1") (pin "3-38") (pinfunction "38_3-38") (pintype "passive"))
    )
    (net (code "197") (name "unconnected-(P1C-41-Pad3-41)") (class "Default")
      (node (ref "P1") (pin "3-41") (pinfunction "41_3-41") (pintype "passive"))
    )
    (net (code "198") (name "unconnected-(P1C-42-Pad3-42)") (class "Default")
      (node (ref "P1") (pin "3-42") (pinfunction "42_3-42") (pintype "passive"))
    )
    (net (code "199") (name "unconnected-(P1C-43-Pad3-43)") (class "Default")
      (node (ref "P1") (pin "3-43") (pinfunction "43_3-43") (pintype "passive"))
    )
    (net (code "200") (name "unconnected-(P1C-44-Pad3-44)") (class "Default")
      (node (ref "P1") (pin "3-44") (pinfunction "44_3-44") (pintype "passive"))
    )
    (net (code "201") (name "unconnected-(P1C-45-Pad3-45)") (class "Default")
      (node (ref "P1") (pin "3-45") (pinfunction "45_3-45") (pintype "passive"))
    )
    (net (code "202") (name "unconnected-(P1C-46-Pad3-46)") (class "Default")
      (node (ref "P1") (pin "3-46") (pinfunction "46_3-46") (pintype "passive"))
    )
    (net (code "203") (name "unconnected-(P1C-47-Pad3-47)") (class "Default")
      (node (ref "P1") (pin "3-47") (pinfunction "47_3-47") (pintype "passive"))
    )
    (net (code "204") (name "unconnected-(P1C-48-Pad3-48)") (class "Default")
      (node (ref "P1") (pin "3-48") (pinfunction "48_3-48") (pintype "passive"))
    )
    (net (code "205") (name "unconnected-(P1C-52-Pad3-52)") (class "Default")
      (node (ref "P1") (pin "3-52") (pinfunction "52_3-52") (pintype "passive"))
    )
    (net (code "206") (name "unconnected-(P1C-53-Pad3-53)") (class "Default")
      (node (ref "P1") (pin "3-53") (pinfunction "53_3-53") (pintype "passive"))
    )
    (net (code "207") (name "unconnected-(P1C-54-Pad3-54)") (class "Default")
      (node (ref "P1") (pin "3-54") (pinfunction "54_3-54") (pintype "passive"))
    )
    (net (code "208") (name "unconnected-(P1C-55-Pad3-55)") (class "Default")
      (node (ref "P1") (pin "3-55") (pinfunction "55_3-55") (pintype "passive"))
    )
    (net (code "209") (name "unconnected-(P1C-56-Pad3-56)") (class "Default")
      (node (ref "P1") (pin "3-56") (pinfunction "56_3-56") (pintype "passive"))
    )
    (net (code "210") (name "unconnected-(P1C-57-Pad3-57)") (class "Default")
      (node (ref "P1") (pin "3-57") (pinfunction "57_3-57") (pintype "passive"))
    )
    (net (code "211") (name "unconnected-(P1C-58-Pad3-58)") (class "Default")
      (node (ref "P1") (pin "3-58") (pinfunction "58_3-58") (pintype "passive"))
    )
    (net (code "212") (name "unconnected-(P1C-61-Pad3-61)") (class "Default")
      (node (ref "P1") (pin "3-61") (pinfunction "61_3-61") (pintype "passive"))
    )
    (net (code "213") (name "unconnected-(P1C-62-Pad3-62)") (class "Default")
      (node (ref "P1") (pin "3-62") (pinfunction "62_3-62") (pintype "passive"))
    )
    (net (code "214") (name "unconnected-(P1C-63-Pad3-63)") (class "Default")
      (node (ref "P1") (pin "3-63") (pinfunction "63_3-63") (pintype "passive"))
    )
    (net (code "215") (name "unconnected-(P1C-64-Pad3-64)") (class "Default")
      (node (ref "P1") (pin "3-64") (pinfunction "64_3-64") (pintype "passive"))
    )
    (net (code "216") (name "unconnected-(P1C-65-Pad3-65)") (class "Default")
      (node (ref "P1") (pin "3-65") (pinfunction "65_3-65") (pintype "passive"))
    )
    (net (code "217") (name "unconnected-(P1C-66-Pad3-66)") (class "Default")
      (node (ref "P1") (pin "3-66") (pinfunction "66_3-66") (pintype "passive"))
    )
    (net (code "218") (name "unconnected-(P1C-67-Pad3-67)") (class "Default")
      (node (ref "P1") (pin "3-67") (pinfunction "67_3-67") (pintype "passive"))
    )
    (net (code "219") (name "unconnected-(P1C-68-Pad3-68)") (class "Default")
      (node (ref "P1") (pin "3-68") (pinfunction "68_3-68") (pintype "passive"))
    )
    (net (code "220") (name "unconnected-(P1C-71-Pad3-71)") (class "Default")
      (node (ref "P1") (pin "3-71") (pinfunction "71_3-71") (pintype "passive"))
    )
    (net (code "221") (name "unconnected-(P1C-72-Pad3-72)") (class "Default")
      (node (ref "P1") (pin "3-72") (pinfunction "72_3-72") (pintype "passive"))
    )
    (net (code "222") (name "unconnected-(P1C-73-Pad3-73)") (class "Default")
      (node (ref "P1") (pin "3-73") (pinfunction "73_3-73") (pintype "passive"))
    )
    (net (code "223") (name "unconnected-(P1C-74-Pad3-74)") (class "Default")
      (node (ref "P1") (pin "3-74") (pinfunction "74_3-74") (pintype "passive"))
    )
    (net (code "224") (name "unconnected-(P1C-75-Pad3-75)") (class "Default")
      (node (ref "P1") (pin "3-75") (pinfunction "75_3-75") (pintype "passive+no_connect"))
    )
    (net (code "225") (name "unconnected-(P1C-76-Pad3-76)") (class "Default")
      (node (ref "P1") (pin "3-76") (pinfunction "76_3-76") (pintype "passive+no_connect"))
    )
    (net (code "226") (name "unconnected-(P1D-1-Pad4-1)") (class "Default")
      (node (ref "P1") (pin "4-1") (pinfunction "1_4-1") (pintype "passive+no_connect"))
    )
    (net (code "227") (name "unconnected-(P1D-2-Pad4-2)") (class "Default")
      (node (ref "P1") (pin "4-2") (pinfunction "2_4-2") (pintype "passive+no_connect"))
    )
    (net (code "228") (name "unconnected-(P1D-3-Pad4-3)") (class "Default")
      (node (ref "P1") (pin "4-3") (pinfunction "3_4-3") (pintype "passive+no_connect"))
    )
    (net (code "229") (name "unconnected-(P1D-4-Pad4-4)") (class "Default")
      (node (ref "P1") (pin "4-4") (pinfunction "4_4-4") (pintype "passive+no_connect"))
    )
    (net (code "230") (name "unconnected-(P1D-5-Pad4-5)") (class "Default")
      (node (ref "P1") (pin "4-5") (pinfunction "5_4-5") (pintype "passive+no_connect"))
    )
    (net (code "231") (name "unconnected-(P1D-6-Pad4-6)") (class "Default")
      (node (ref "P1") (pin "4-6") (pinfunction "6_4-6") (pintype "passive+no_connect"))
    )
    (net (code "232") (name "unconnected-(P1D-7-Pad4-7)") (class "Default")
      (node (ref "P1") (pin "4-7") (pinfunction "7_4-7") (pintype "passive+no_connect"))
    )
    (net (code "233") (name "unconnected-(P1D-8-Pad4-8)") (class "Default")
      (node (ref "P1") (pin "4-8") (pinfunction "8_4-8") (pintype "passive+no_connect"))
    )
    (net (code "234") (name "unconnected-(P1D-11-Pad4-11)") (class "Default")
      (node (ref "P1") (pin "4-11") (pinfunction "11_4-11") (pintype "passive+no_connect"))
    )
    (net (code "235") (name "unconnected-(P1D-13-Pad4-13)") (class "Default")
      (node (ref "P1") (pin "4-13") (pinfunction "13_4-13") (pintype "passive+no_connect"))
    )
    (net (code "236") (name "unconnected-(P1D-16-Pad4-16)") (class "Default")
      (node (ref "P1") (pin "4-16") (pinfunction "16_4-16") (pintype "passive"))
    )
    (net (code "237") (name "unconnected-(P1D-22-Pad4-22)") (class "Default")
      (node (ref "P1") (pin "4-22") (pinfunction "22_4-22") (pintype "passive"))
    )
    (net (code "238") (name "unconnected-(P1D-28-Pad4-28)") (class "Default")
      (node (ref "P1") (pin "4-28") (pinfunction "28_4-28") (pintype "passive"))
    )
    (net (code "239") (name "unconnected-(P1D-34-Pad4-34)") (class "Default")
      (node (ref "P1") (pin "4-34") (pinfunction "34_4-34") (pintype "passive"))
    )
    (net (code "240") (name "unconnected-(P1D-41-Pad4-41)") (class "Default")
      (node (ref "P1") (pin "4-41") (pinfunction "41_4-41") (pintype "passive"))
    )
    (net (code "241") (name "unconnected-(P1D-42-Pad4-42)") (class "Default")
      (node (ref "P1") (pin "4-42") (pinfunction "42_4-42") (pintype "passive"))
    )
    (net (code "242") (name "unconnected-(P1D-43-Pad4-43)") (class "Default")
      (node (ref "P1") (pin "4-43") (pinfunction "43_4-43") (pintype "passive"))
    )
    (net (code "243") (name "unconnected-(P1D-44-Pad4-44)") (class "Default")
      (node (ref "P1") (pin "4-44") (pinfunction "44_4-44") (pintype "passive"))
    )
    (net (code "244") (name "unconnected-(P1D-45-Pad4-45)") (class "Default")
      (node (ref "P1") (pin "4-45") (pinfunction "45_4-45") (pintype "passive"))
    )
    (net (code "245") (name "unconnected-(P1D-46-Pad4-46)") (class "Default")
      (node (ref "P1") (pin "4-46") (pinfunction "46_4-46") (pintype "passive"))
    )
    (net (code "246") (name "unconnected-(P1D-47-Pad4-47)") (class "Default")
      (node (ref "P1") (pin "4-47") (pinfunction "47_4-47") (pintype "passive"))
    )
    (net (code "247") (name "unconnected-(P1D-48-Pad4-48)") (class "Default")
      (node (ref "P1") (pin "4-48") (pinfunction "48_4-48") (pintype "passive"))
    )
    (net (code "248") (name "unconnected-(P1D-51-Pad4-51)") (class "Default")
      (node (ref "P1") (pin "4-51") (pinfunction "51_4-51") (pintype "passive"))
    )
    (net (code "249") (name "unconnected-(P1D-52-Pad4-52)") (class "Default")
      (node (ref "P1") (pin "4-52") (pinfunction "52_4-52") (pintype "passive"))
    )
    (net (code "250") (name "unconnected-(P1D-53-Pad4-53)") (class "Default")
      (node (ref "P1") (pin "4-53") (pinfunction "53_4-53") (pintype "passive"))
    )
    (net (code "251") (name "unconnected-(P1D-54-Pad4-54)") (class "Default")
      (node (ref "P1") (pin "4-54") (pinfunction "54_4-54") (pintype "passive"))
    )
    (net (code "252") (name "unconnected-(P1D-55-Pad4-55)") (class "Default")
      (node (ref "P1") (pin "4-55") (pinfunction "55_4-55") (pintype "passive"))
    )
    (net (code "253") (name "unconnected-(P1D-56-Pad4-56)") (class "Default")
      (node (ref "P1") (pin "4-56") (pinfunction "56_4-56") (pintype "passive"))
    )
    (net (code "254") (name "unconnected-(P1D-57-Pad4-57)") (class "Default")
      (node (ref "P1") (pin "4-57") (pinfunction "57_4-57") (pintype "passive"))
    )
    (net (code "255") (name "unconnected-(P1D-58-Pad4-58)") (class "Default")
      (node (ref "P1") (pin "4-58") (pinfunction "58_4-58") (pintype "passive"))
    )
    (net (code "256") (name "unconnected-(P1D-61-Pad4-61)") (class "Default")
      (node (ref "P1") (pin "4-61") (pinfunction "61_4-61") (pintype "passive"))
    )
    (net (code "257") (name "unconnected-(P1D-62-Pad4-62)") (class "Default")
      (node (ref "P1") (pin "4-62") (pinfunction "62_4-62") (pintype "passive"))
    )
    (net (code "258") (name "unconnected-(P1D-63-Pad4-63)") (class "Default")
      (node (ref "P1") (pin "4-63") (pinfunction "63_4-63") (pintype "passive"))
    )
    (net (code "259") (name "unconnected-(P1D-64-Pad4-64)") (class "Default")
      (node (ref "P1") (pin "4-64") (pinfunction "64_4-64") (pintype "passive"))
    )
    (net (code "260") (name "unconnected-(P1D-65-Pad4-65)") (class "Default")
      (node (ref "P1") (pin "4-65") (pinfunction "65_4-65") (pintype "passive"))
    )
    (net (code "261") (name "unconnected-(P1D-66-Pad4-66)") (class "Default")
      (node (ref "P1") (pin "4-66") (pinfunction "66_4-66") (pintype "passive"))
    )
    (net (code "262") (name "unconnected-(P1D-67-Pad4-67)") (class "Default")
      (node (ref "P1") (pin "4-67") (pinfunction "67_4-67") (pintype "passive"))
    )
    (net (code "263") (name "unconnected-(P1D-68-Pad4-68)") (class "Default")
      (node (ref "P1") (pin "4-68") (pinfunction "68_4-68") (pintype "passive"))
    )
    (net (code "264") (name "unconnected-(P1D-71-Pad4-71)") (class "Default")
      (node (ref "P1") (pin "4-71") (pinfunction "71_4-71") (pintype "passive"))
    )
    (net (code "265") (name "unconnected-(P1D-72-Pad4-72)") (class "Default")
      (node (ref "P1") (pin "4-72") (pinfunction "72_4-72") (pintype "passive"))
    )
    (net (code "266") (name "unconnected-(P1D-73-Pad4-73)") (class "Default")
      (node (ref "P1") (pin "4-73") (pinfunction "73_4-73") (pintype "passive"))
    )
    (net (code "267") (name "unconnected-(P1D-74-Pad4-74)") (class "Default")
      (node (ref "P1") (pin "4-74") (pinfunction "74_4-74") (pintype "passive"))
    )
    (net (code "268") (name "unconnected-(P1D-75-Pad4-75)") (class "Default")
      (node (ref "P1") (pin "4-75") (pinfunction "75_4-75") (pintype "passive"))
    )
    (net (code "269") (name "unconnected-(P1D-76-Pad4-76)") (class "Default")
      (node (ref "P1") (pin "4-76") (pinfunction "76_4-76") (pintype "passive"))
    )
    (net (code "270") (name "unconnected-(P1D-77-Pad4-77)") (class "Default")
      (node (ref "P1") (pin "4-77") (pinfunction "77_4-77") (pintype "passive"))
    )
    (net (code "271") (name "unconnected-(P1D-78-Pad4-78)") (class "Default")
      (node (ref "P1") (pin "4-78") (pinfunction "78_4-78") (pintype "passive"))
    )
    (net (code "272") (name "unconnected-(P1D-79-Pad4-79)") (class "Default")
      (node (ref "P1") (pin "4-79") (pinfunction "79_4-79") (pintype "passive+no_connect"))
    )
    (net (code "273") (name "unconnected-(P1D-80-Pad4-80)") (class "Default")
      (node (ref "P1") (pin "4-80") (pinfunction "80_4-80") (pintype "passive+no_connect"))
    )
  )
)
